# 20to10pin.net
KiCad netlist of a schematic drawn in Altium Designer
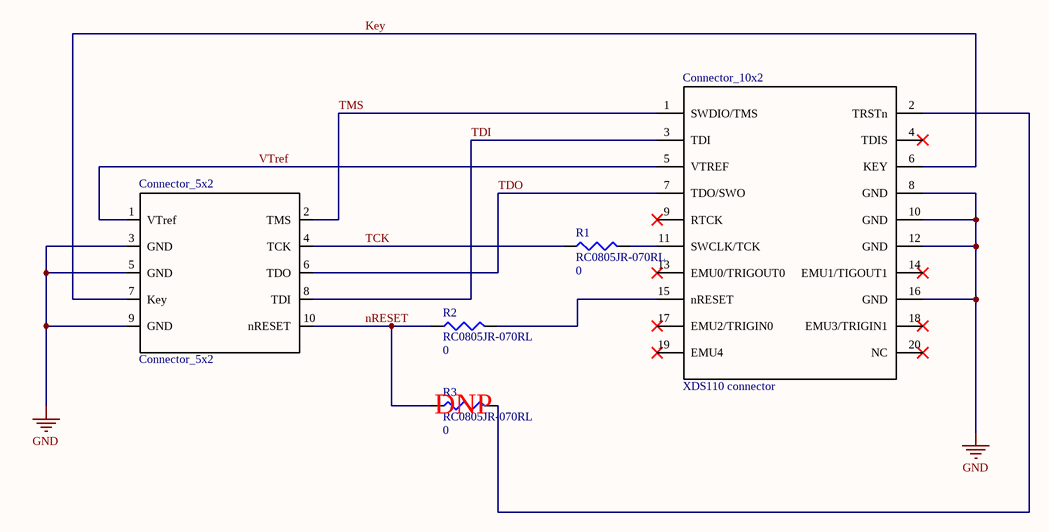
[diagram p0: 20to10pin.SchDoc]

(export (version "E")
  (design (tool "Eeschema 10.0.6"))
  (components
    (comp (ref "Connector_5x2")
      (value "Connector_5x2")
      (footprint "5x2 pin")
      (libsource (lib "Schlib1") (part "Connector_5x2"))
    )
    (comp (ref "Connector_10x2")
      (value "XDS110 connector")
      (footprint "10x2 pin")
      (libsource (lib "Schlib1") (part "XDS110 connector"))
    )
    (comp (ref "R1")
      (value "RC0805JR-070RL")
      (footprint "J1-0603")
      (description "Resistor")
      (fields (field (name "ALTIUM_VALUE") "0") (field (name "PUBLISHER") "Altium Limited"))
      (libsource (lib "Miscellaneous Devices") (part "Res3"))
    )
    (comp (ref "R2")
      (value "RC0805JR-070RL")
      (footprint "J1-0603")
      (description "Resistor")
      (fields (field (name "ALTIUM_VALUE") "0") (field (name "PUBLISHER") "Altium Limited"))
      (libsource (lib "Miscellaneous Devices") (part "Res3"))
    )
    (comp (ref "R3")
      (value "RC0805JR-070RL")
      (footprint "J1-0603")
      (description "Resistor")
      (fields (field (name "ALTIUM_VALUE") "0") (field (name "PUBLISHER") "Altium Limited"))
      (libsource (lib "Miscellaneous Devices") (part "Res3"))
    )
  )
  (nets
    (net (code "1") (name "/Key") (class "Default")
      (node (ref "Connector_10x2") (pin "6") (pinfunction "KEY_6") (pintype "passive"))
      (node (ref "Connector_5x2") (pin "7") (pinfunction "Key_7") (pintype "passive"))
    )
    (net (code "2") (name "/TCK") (class "Default")
      (node (ref "Connector_5x2") (pin "4") (pinfunction "TCK_4") (pintype "passive"))
      (node (ref "R1") (pin "1") (pinfunction "1_1") (pintype "passive"))
    )
    (net (code "3") (name "/TDI") (class "Default")
      (node (ref "Connector_10x2") (pin "3") (pinfunction "TDI_3") (pintype "passive"))
      (node (ref "Connector_5x2") (pin "8") (pinfunction "TDI_8") (pintype "passive"))
    )
    (net (code "4") (name "/TDO") (class "Default")
      (node (ref "Connector_10x2") (pin "7") (pinfunction "TDO/SWO_7") (pintype "passive"))
      (node (ref "Connector_5x2") (pin "6") (pinfunction "TDO_6") (pintype "passive"))
    )
    (net (code "5") (name "/TMS") (class "Default")
      (node (ref "Connector_10x2") (pin "1") (pinfunction "SWDIO/TMS_1") (pintype "passive"))
      (node (ref "Connector_5x2") (pin "2") (pinfunction "TMS_2") (pintype "passive"))
    )
    (net (code "6") (name "/VTref") (class "Default")
      (node (ref "Connector_10x2") (pin "5") (pinfunction "VTREF_5") (pintype "passive"))
      (node (ref "Connector_5x2") (pin "1") (pinfunction "VTref_1") (pintype "passive"))
    )
    (net (code "7") (name "/nRESET") (class "Default")
      (node (ref "Connector_5x2") (pin "10") (pinfunction "nRESET_10") (pintype "passive"))
      (node (ref "R2") (pin "1") (pinfunction "1_1") (pintype "passive"))
      (node (ref "R3") (pin "1") (pinfunction "1_1") (pintype "passive"))
    )
    (net (code "8") (name "GND") (class "Default")
      (node (ref "Connector_10x2") (pin "10") (pinfunction "GND_10") (pintype "passive"))
      (node (ref "Connector_10x2") (pin "12") (pinfunction "GND_12") (pintype "passive"))
      (node (ref "Connector_10x2") (pin "16") (pinfunction "GND_16") (pintype "passive"))
      (node (ref "Connector_10x2") (pin "8") (pinfunction "GND_8") (pintype "passive"))
      (node (ref "Connector_5x2") (pin "3") (pinfunction "GND_3") (pintype "passive"))
      (node (ref "Connector_5x2") (pin "5") (pinfunction "GND_5") (pintype "passive"))
      (node (ref "Connector_5x2") (pin "9") (pinfunction "GND_9") (pintype "passive"))
    )
    (net (code "9") (name "Net-(Connector_10x2-SWCLK{slash}TCK)") (class "Default")
      (node (ref "Connector_10x2") (pin "11") (pinfunction "SWCLK/TCK_11") (pintype "passive"))
      (node (ref "R1") (pin "2") (pinfunction "2_2") (pintype "passive"))
    )
    (net (code "10") (name "Net-(Connector_10x2-TRSTn)") (class "Default")
      (node (ref "Connector_10x2") (pin "2") (pinfunction "TRSTn_2") (pintype "passive"))
      (node (ref "R3") (pin "2") (pinfunction "2_2") (pintype "passive"))
    )
    (net (code "11") (name "Net-(Connector_10x2-nRESET)") (class "Default")
      (node (ref "Connector_10x2") (pin "15") (pinfunction "nRESET_15") (pintype "passive"))
      (node (ref "R2") (pin "2") (pinfunction "2_2") (pintype "passive"))
    )
    (net (code "12") (name "unconnected-(Connector_10x2-EMU0{slash}TRIGOUT0-Pad13)") (class "Default")
      (node (ref "Connector_10x2") (pin "13") (pinfunction "EMU0/TRIGOUT0_13") (pintype "passive+no_connect"))
    )
    (net (code "13") (name "unconnected-(Connector_10x2-EMU1{slash}TIGOUT1-Pad14)") (class "Default")
      (node (ref "Connector_10x2") (pin "14") (pinfunction "EMU1/TIGOUT1_14") (pintype "passive+no_connect"))
    )
    (net (code "14") (name "unconnected-(Connector_10x2-EMU2{slash}TRIGIN0-Pad17)") (class "Default")
      (node (ref "Connector_10x2") (pin "17") (pinfunction "EMU2/TRIGIN0_17") (pintype "passive+no_connect"))
    )
    (net (code "15") (name "unconnected-(Connector_10x2-EMU3{slash}TRIGIN1-Pad18)") (class "Default")
      (node (ref "Connector_10x2") (pin "18") (pinfunction "EMU3/TRIGIN1_18") (pintype "passive+no_connect"))
    )
    (net (code "16") (name "unconnected-(Connector_10x2-EMU4-Pad19)") (class "Default")
      (node (ref "Connector_10x2") (pin "19") (pinfunction "EMU4_19") (pintype "passive+no_connect"))
    )
    (net (code "17") (name "unconnected-(Connector_10x2-NC-Pad20)") (class "Default")
      (node (ref "Connector_10x2") (pin "20") (pinfunction "NC_20") (pintype "passive+no_connect"))
    )
    (net (code "18") (name "unconnected-(Connector_10x2-RTCK-Pad9)") (class "Default")
      (node (ref "Connector_10x2") (pin "9") (pinfunction "RTCK_9") (pintype "passive+no_connect"))
    )
    (net (code "19") (name "unconnected-(Connector_10x2-TDIS-Pad4)") (class "Default")
      (node (ref "Connector_10x2") (pin "4") (pinfunction "TDIS_4") (pintype "passive+no_connect"))
    )
  )
)
